# MOSFET.net
KiCad netlist of a schematic drawn in Altium Designer
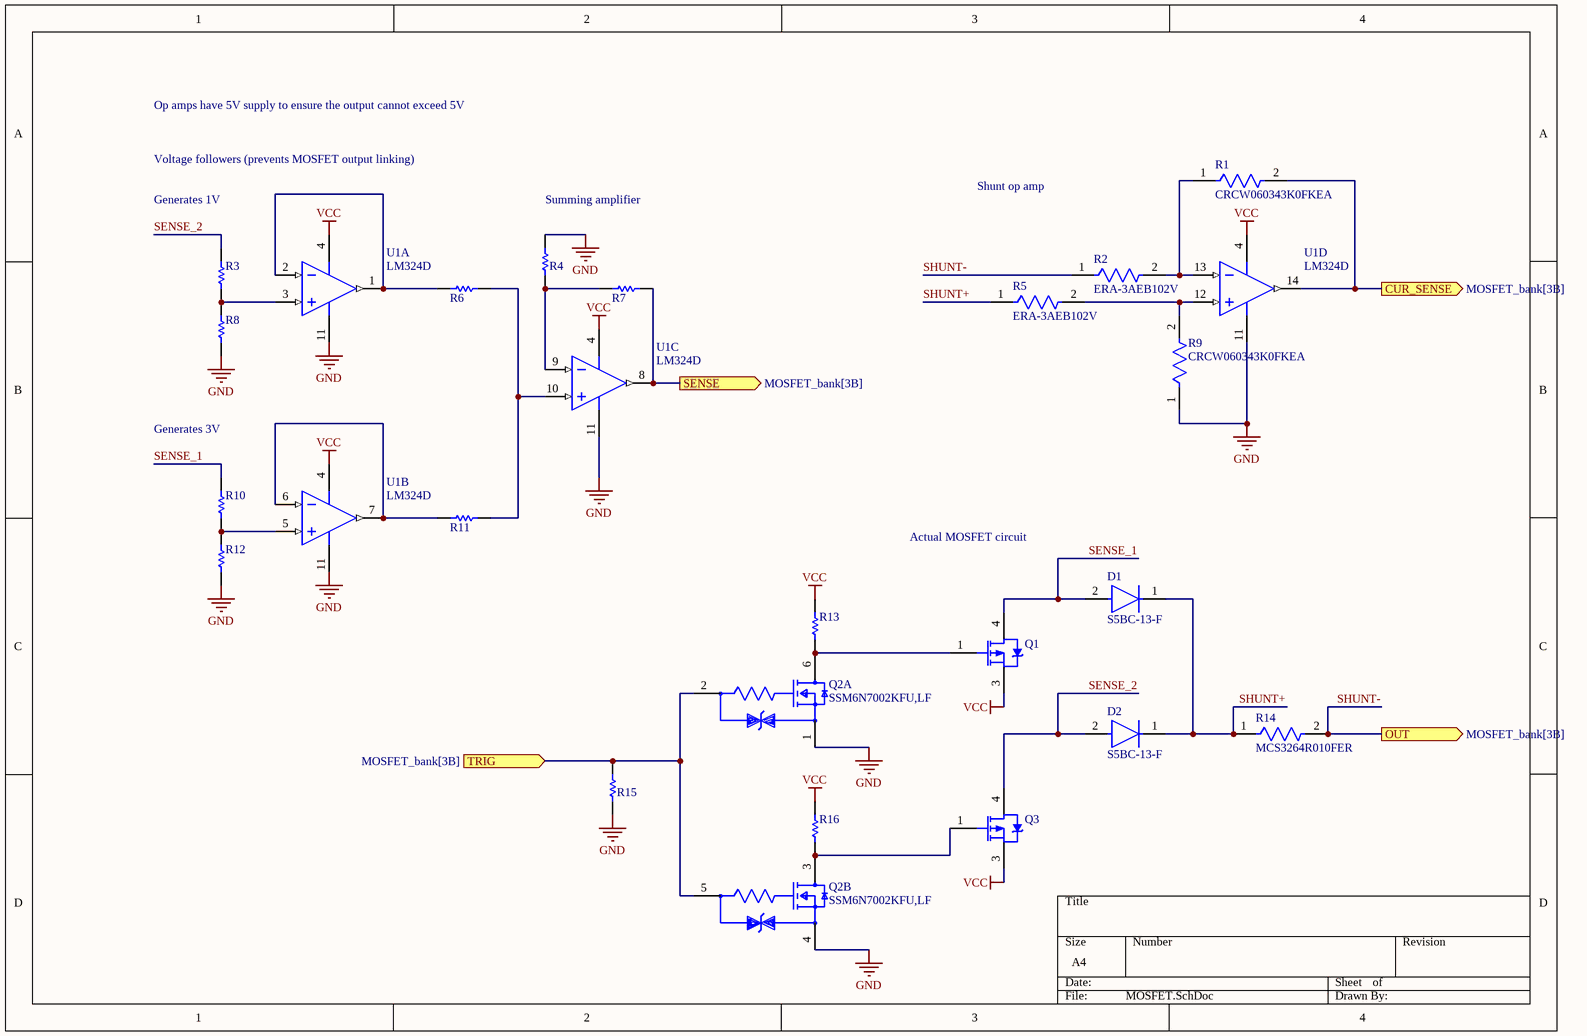
[diagram p0: MOSFET.SchDoc]

(export (version "E")
  (design (tool "Eeschema 10.0.6"))
  (components
    (comp (ref "D1")
      (value "S5BC-13-F")
      (footprint "FP-SMC-MFG")
      (description "DIODE GEN PURP 100V 5A SMC")
      (fields
        (field (name "OCTOPART") "https://octopart.com/s5bc-13-f-diodes+inc.-333396")
        (field (name "MANUFACTURER") "Diodes Inc.")
      )
      (libsource (lib "Altium Content Vault") (part "d7152d700b627762746794eb795d46e"))
    )
    (comp (ref "D2")
      (value "S5BC-13-F")
      (footprint "FP-SMC-MFG")
      (description "DIODE GEN PURP 100V 5A SMC")
      (fields
        (field (name "OCTOPART") "https://octopart.com/s5bc-13-f-diodes+inc.-333396")
        (field (name "MANUFACTURER") "Diodes Inc.")
      )
      (libsource (lib "Altium Content Vault") (part "d7152d700b627762746794eb795d46e"))
    )
    (comp (ref "Q1")
      (value "NTD25P03LT4G")
      (footprint "ONSC-DPAK-3-369C-01_V")
      (description "Power MOSFET, -25 A, -30 V, Logic Level P-Channel, 3-Pin DPAK, Pb-Free, Tape and Reel")
      (fields (field (name "MANUFACTURER") "On Semiconductor"))
      (libsource (lib "Altium Content Vault") (part "ONSC-PMOS-G1S3D4-3_B"))
    )
    (comp (ref "Q2")
      (value "SSM6N7002KFU,LF")
      (footprint "FP-SSOP6-P-0_65A-MFG")
      (description "MOSFET 2N-CH 60V 0.3A")
      (libsource (lib "Altium Content Vault") (part "088aa6ac103fdeebe0d1c52ece6b7b9"))
    )
    (comp (ref "Q3")
      (value "NTD25P03LT4G")
      (footprint "ONSC-DPAK-3-369C-01_V")
      (description "Power MOSFET, -25 A, -30 V, Logic Level P-Channel, 3-Pin DPAK, Pb-Free, Tape and Reel")
      (fields (field (name "MANUFACTURER") "On Semiconductor"))
      (libsource (lib "Altium Content Vault") (part "ONSC-PMOS-G1S3D4-3_B"))
    )
    (comp (ref "R1")
      (value "CRCW060343K0FKEA")
      (footprint "FP-CRCW0603-e3-IPC_A")
      (description "RES Thick Film, 43kΩ, 1%, 0.1W, 100ppm/°C, 0603")
      (fields (field (name "TOLERANCE") "1%"))
      (libsource (lib "Altium Content Vault") (part "1029c3af85768c4190bb7ad29bc67b5"))
    )
    (comp (ref "R2")
      (value "ERA-3AEB102V")
      (footprint "FP-ERA3A-IPC_C")
      (description "RES SMD 1K OHM 0.1% 1/10W 0603")
      (fields (field (name "TOLERANCE") "0.1%"))
      (libsource (lib "Altium Content Vault") (part "1029c3af85768c4190bb7ad29bc67b5"))
    )
    (comp (ref "R3")
      (value "ERJ3EKF1002V")
      (footprint "RESC1609X55X30LL15T15")
      (description "Chip Resistor, 10 KOhm, +/- 1%, 0.1 W, -55 to 155 degC, 0603 (1608 Metric), RoHS, Tape and Reel")
      (fields (field (name "TOLERANCE") "1%") (field (name "MANUFACTURER") "Panasonic"))
      (libsource (lib "Altium Content Vault") (part "RES-2"))
    )
    (comp (ref "R4")
      (value "ERJ3EKF1002V")
      (footprint "RESC1609X55X30LL15T15")
      (description "Chip Resistor, 10 KOhm, +/- 1%, 0.1 W, -55 to 155 degC, 0603 (1608 Metric), RoHS, Tape and Reel")
      (fields (field (name "TOLERANCE") "1%") (field (name "MANUFACTURER") "Panasonic"))
      (libsource (lib "Altium Content Vault") (part "RES-2"))
    )
    (comp (ref "R5")
      (value "ERA-3AEB102V")
      (footprint "FP-ERA3A-IPC_C")
      (description "RES SMD 1K OHM 0.1% 1/10W 0603")
      (fields (field (name "TOLERANCE") "0.1%"))
      (libsource (lib "Altium Content Vault") (part "1029c3af85768c4190bb7ad29bc67b5"))
    )
    (comp (ref "R6")
      (value "ERJ3EKF1002V")
      (footprint "RESC1609X55X30LL15T15")
      (description "Chip Resistor, 10 KOhm, +/- 1%, 0.1 W, -55 to 155 degC, 0603 (1608 Metric), RoHS, Tape and Reel")
      (fields (field (name "TOLERANCE") "1%") (field (name "MANUFACTURER") "Panasonic"))
      (libsource (lib "Altium Content Vault") (part "RES-2"))
    )
    (comp (ref "R7")
      (value "ERJ3EKF1002V")
      (footprint "RESC1609X55X30LL15T15")
      (description "Chip Resistor, 10 KOhm, +/- 1%, 0.1 W, -55 to 155 degC, 0603 (1608 Metric), RoHS, Tape and Reel")
      (fields (field (name "TOLERANCE") "1%") (field (name "MANUFACTURER") "Panasonic"))
      (libsource (lib "Altium Content Vault") (part "RES-2"))
    )
    (comp (ref "R8")
      (value "ERA-3AEB751V")
      (footprint "RESC1608X55X30ML20T20")
      (fields (field (name "MANUFACTURER") "Panasonic"))
      (libsource (lib "Altium Content Vault") (part "RES"))
    )
    (comp (ref "R9")
      (value "CRCW060343K0FKEA")
      (footprint "FP-CRCW0603-e3-IPC_A")
      (description "RES Thick Film, 43kΩ, 1%, 0.1W, 100ppm/°C, 0603")
      (fields (field (name "TOLERANCE") "1%"))
      (libsource (lib "Altium Content Vault") (part "1029c3af85768c4190bb7ad29bc67b5"))
    )
    (comp (ref "R10")
      (value "ERJ3EKF1002V")
      (footprint "RESC1609X55X30LL15T15")
      (description "Chip Resistor, 10 KOhm, +/- 1%, 0.1 W, -55 to 155 degC, 0603 (1608 Metric), RoHS, Tape and Reel")
      (fields (field (name "TOLERANCE") "1%") (field (name "MANUFACTURER") "Panasonic"))
      (libsource (lib "Altium Content Vault") (part "RES-2"))
    )
    (comp (ref "R11")
      (value "ERJ3EKF1002V")
      (footprint "RESC1609X55X30LL15T15")
      (description "Chip Resistor, 10 KOhm, +/- 1%, 0.1 W, -55 to 155 degC, 0603 (1608 Metric), RoHS, Tape and Reel")
      (fields (field (name "TOLERANCE") "1%") (field (name "MANUFACTURER") "Panasonic"))
      (libsource (lib "Altium Content Vault") (part "RES-2"))
    )
    (comp (ref "R12")
      (value "ERA3AEB242V")
      (footprint "RESC1608X55X30NL20T20")
      (fields (field (name "MANUFACTURER") "Panasonic"))
      (libsource (lib "Altium Content Vault") (part "RES"))
    )
    (comp (ref "R13")
      (value "ERJ3EKF1002V")
      (footprint "RESC1609X55X30LL15T15")
      (description "Chip Resistor, 10 KOhm, +/- 1%, 0.1 W, -55 to 155 degC, 0603 (1608 Metric), RoHS, Tape and Reel")
      (fields (field (name "TOLERANCE") "1%") (field (name "MANUFACTURER") "Panasonic"))
      (libsource (lib "Altium Content Vault") (part "RES-2"))
    )
    (comp (ref "R14")
      (value "MCS3264R010FER")
      (footprint "FP-MCS3264-MFG")
      (description "RES SMD 10 MOHM 1% 2W 3264")
      (fields (field (name "TOLERANCE") "1%"))
      (libsource (lib "Altium Content Vault") (part "1029c3af85768c4190bb7ad29bc67b5"))
    )
    (comp (ref "R15")
      (value "ERJ3EKF1002V")
      (footprint "RESC1609X55X30LL15T15")
      (description "Chip Resistor, 10 KOhm, +/- 1%, 0.1 W, -55 to 155 degC, 0603 (1608 Metric), RoHS, Tape and Reel")
      (fields (field (name "TOLERANCE") "1%") (field (name "MANUFACTURER") "Panasonic"))
      (libsource (lib "Altium Content Vault") (part "RES-2"))
    )
    (comp (ref "R16")
      (value "ERJ3EKF1002V")
      (footprint "RESC1609X55X30LL15T15")
      (description "Chip Resistor, 10 KOhm, +/- 1%, 0.1 W, -55 to 155 degC, 0603 (1608 Metric), RoHS, Tape and Reel")
      (fields (field (name "TOLERANCE") "1%") (field (name "MANUFACTURER") "Panasonic"))
      (libsource (lib "Altium Content Vault") (part "RES-2"))
    )
    (comp (ref "U1")
      (value "LM324D")
      (footprint "D0014A_L")
      (fields (field (name "MANUFACTURER") "Texas Instruments"))
      (libsource (lib "Altium Content Vault") (part "TI-LMX24_2902X-X14"))
    )
  )
  (nets
    (net (code "1") (name "/CUR_SENSE") (class "Default")
      (node (ref "R1") (pin "2") (pinfunction "2_2") (pintype "passive"))
      (node (ref "U1") (pin "14") (pinfunction "4OUT_14") (pintype "output"))
    )
    (net (code "2") (name "/SENSE") (class "Default")
      (node (ref "R7") (pin "1") (pinfunction "1_1") (pintype "passive"))
      (node (ref "U1") (pin "8") (pinfunction "3OUT_8") (pintype "output"))
    )
    (net (code "3") (name "/SENSE_1") (class "Default")
      (node (ref "D1") (pin "2") (pinfunction "A_2") (pintype "passive"))
      (node (ref "Q1") (pin "4") (pinfunction "D_4") (pintype "passive"))
      (node (ref "R10") (pin "2") (pinfunction "2_2") (pintype "passive"))
    )
    (net (code "4") (name "/SENSE_2") (class "Default")
      (node (ref "D2") (pin "2") (pinfunction "A_2") (pintype "passive"))
      (node (ref "Q3") (pin "4") (pinfunction "D_4") (pintype "passive"))
      (node (ref "R3") (pin "2") (pinfunction "2_2") (pintype "passive"))
    )
    (net (code "5") (name "/SHUNT+") (class "Default")
      (node (ref "D1") (pin "1") (pinfunction "C_1") (pintype "passive"))
      (node (ref "D2") (pin "1") (pinfunction "C_1") (pintype "passive"))
      (node (ref "R14") (pin "1") (pinfunction "1_1") (pintype "passive"))
      (node (ref "R5") (pin "1") (pinfunction "1_1") (pintype "passive"))
    )
    (net (code "6") (name "/SHUNT-") (class "Default")
      (node (ref "R14") (pin "2") (pinfunction "2_2") (pintype "passive"))
      (node (ref "R2") (pin "1") (pinfunction "1_1") (pintype "passive"))
    )
    (net (code "7") (name "/TRIG") (class "Default")
      (node (ref "Q2") (pin "2") (pinfunction "Gate1_2") (pintype "passive"))
      (node (ref "Q2") (pin "5") (pinfunction "Gate2_5") (pintype "passive"))
      (node (ref "R15") (pin "1") (pinfunction "1_1") (pintype "passive"))
    )
    (net (code "8") (name "GND") (class "Default")
      (node (ref "Q2") (pin "1") (pinfunction "Source1_1") (pintype "passive"))
      (node (ref "Q2") (pin "4") (pinfunction "Source2_4") (pintype "passive"))
      (node (ref "R12") (pin "1") (pinfunction "1_1") (pintype "passive"))
      (node (ref "R15") (pin "2") (pinfunction "2_2") (pintype "passive"))
      (node (ref "R4") (pin "1") (pinfunction "1_1") (pintype "passive"))
      (node (ref "R8") (pin "1") (pinfunction "1_1") (pintype "passive"))
      (node (ref "R9") (pin "1") (pinfunction "1_1") (pintype "passive"))
      (node (ref "U1") (pin "11") (pinfunction "GND_11") (pintype "power_in"))
    )
    (net (code "9") (name "Net-(Q1-G)") (class "Default")
      (node (ref "Q1") (pin "1") (pinfunction "G_1") (pintype "passive"))
      (node (ref "Q2") (pin "6") (pinfunction "Drain1_6") (pintype "passive"))
      (node (ref "R13") (pin "1") (pinfunction "1_1") (pintype "passive"))
    )
    (net (code "10") (name "Net-(Q2B-Drain2)") (class "Default")
      (node (ref "Q2") (pin "3") (pinfunction "Drain2_3") (pintype "passive"))
      (node (ref "Q3") (pin "1") (pinfunction "G_1") (pintype "passive"))
      (node (ref "R16") (pin "1") (pinfunction "1_1") (pintype "passive"))
    )
    (net (code "11") (name "Net-(U1A-1IN+)") (class "Default")
      (node (ref "R3") (pin "1") (pinfunction "1_1") (pintype "passive"))
      (node (ref "R8") (pin "2") (pinfunction "2_2") (pintype "passive"))
      (node (ref "U1") (pin "3") (pinfunction "1IN+_3") (pintype "input"))
    )
    (net (code "12") (name "Net-(U1A-1IN-)") (class "Default")
      (node (ref "R6") (pin "2") (pinfunction "2_2") (pintype "passive"))
      (node (ref "U1") (pin "1") (pinfunction "1OUT_1") (pintype "output"))
      (node (ref "U1") (pin "2") (pinfunction "1IN-_2") (pintype "input"))
    )
    (net (code "13") (name "Net-(U1B-2IN+)") (class "Default")
      (node (ref "R10") (pin "1") (pinfunction "1_1") (pintype "passive"))
      (node (ref "R12") (pin "2") (pinfunction "2_2") (pintype "passive"))
      (node (ref "U1") (pin "5") (pinfunction "2IN+_5") (pintype "input"))
    )
    (net (code "14") (name "Net-(U1B-2IN-)") (class "Default")
      (node (ref "R11") (pin "2") (pinfunction "2_2") (pintype "passive"))
      (node (ref "U1") (pin "6") (pinfunction "2IN-_6") (pintype "input"))
      (node (ref "U1") (pin "7") (pinfunction "2OUT_7") (pintype "output"))
    )
    (net (code "15") (name "Net-(U1C-3IN+)") (class "Default")
      (node (ref "R11") (pin "1") (pinfunction "1_1") (pintype "passive"))
      (node (ref "R6") (pin "1") (pinfunction "1_1") (pintype "passive"))
      (node (ref "U1") (pin "10") (pinfunction "3IN+_10") (pintype "input"))
    )
    (net (code "16") (name "Net-(U1C-3IN-)") (class "Default")
      (node (ref "R4") (pin "2") (pinfunction "2_2") (pintype "passive"))
      (node (ref "R7") (pin "2") (pinfunction "2_2") (pintype "passive"))
      (node (ref "U1") (pin "9") (pinfunction "3IN-_9") (pintype "input"))
    )
    (net (code "17") (name "Net-(U1D-4IN+)") (class "Default")
      (node (ref "R5") (pin "2") (pinfunction "2_2") (pintype "passive"))
      (node (ref "R9") (pin "2") (pinfunction "2_2") (pintype "passive"))
      (node (ref "U1") (pin "12") (pinfunction "4IN+_12") (pintype "input"))
    )
    (net (code "18") (name "Net-(U1D-4IN-)") (class "Default")
      (node (ref "R1") (pin "1") (pinfunction "1_1") (pintype "passive"))
      (node (ref "R2") (pin "2") (pinfunction "2_2") (pintype "passive"))
      (node (ref "U1") (pin "13") (pinfunction "4IN-_13") (pintype "input"))
    )
    (net (code "19") (name "VCC") (class "Default")
      (node (ref "Q1") (pin "3") (pinfunction "S_3") (pintype "passive"))
      (node (ref "Q3") (pin "3") (pinfunction "S_3") (pintype "passive"))
      (node (ref "R13") (pin "2") (pinfunction "2_2") (pintype "passive"))
      (node (ref "R16") (pin "2") (pinfunction "2_2") (pintype "passive"))
      (node (ref "U1") (pin "4") (pinfunction "VCC_4") (pintype "power_in"))
    )
  )
)
